# cos_POC.net
KiCad netlist of a schematic drawn in EAGLE
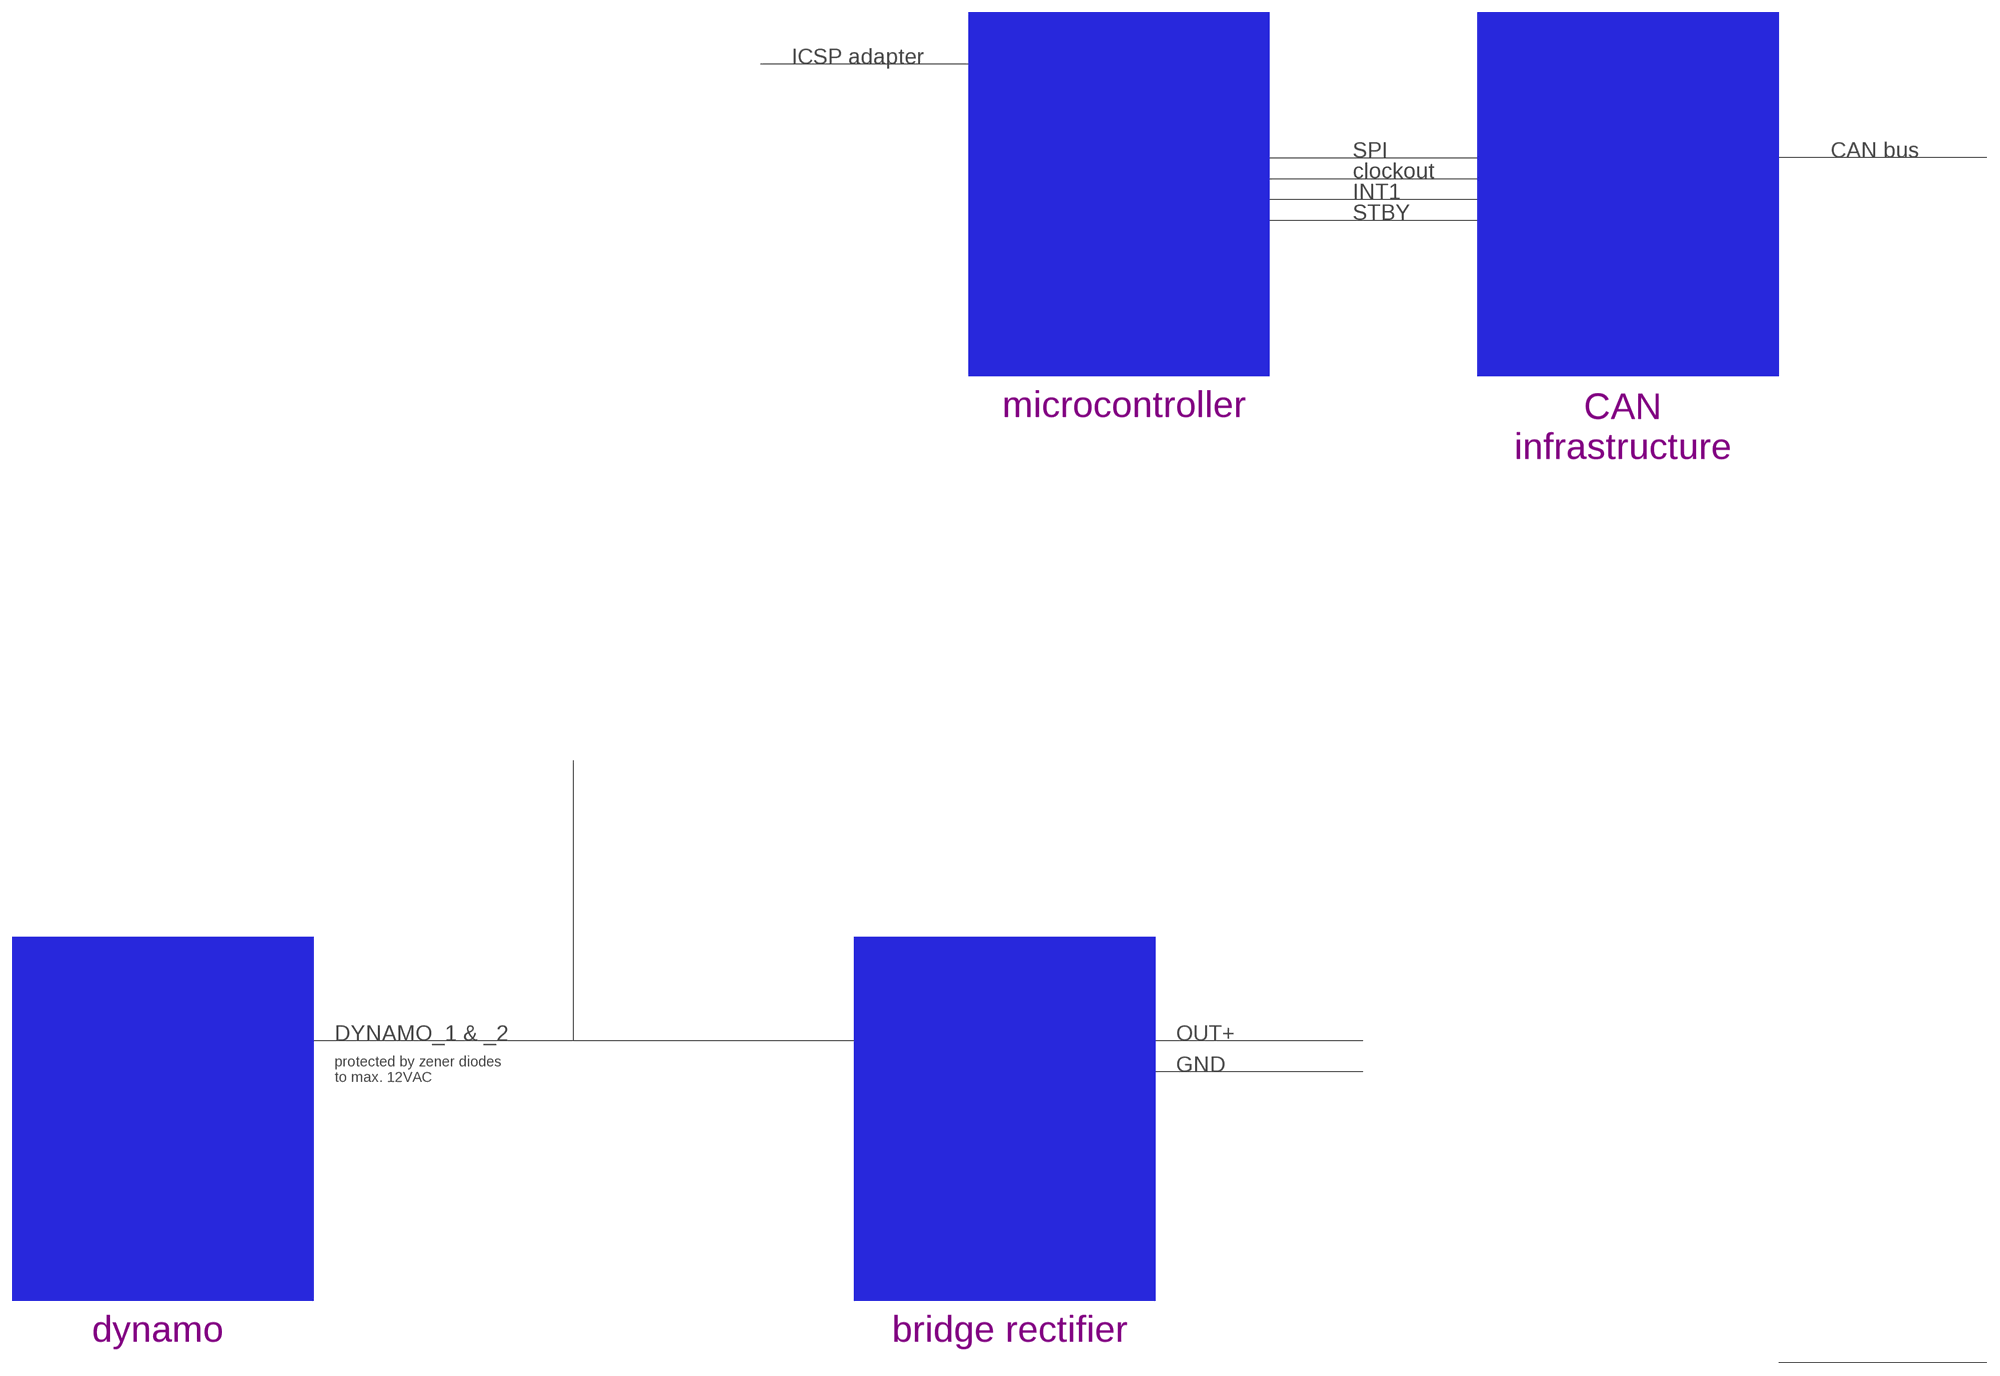
[diagram p0: schematic, sheet 1, part 1 of 3]
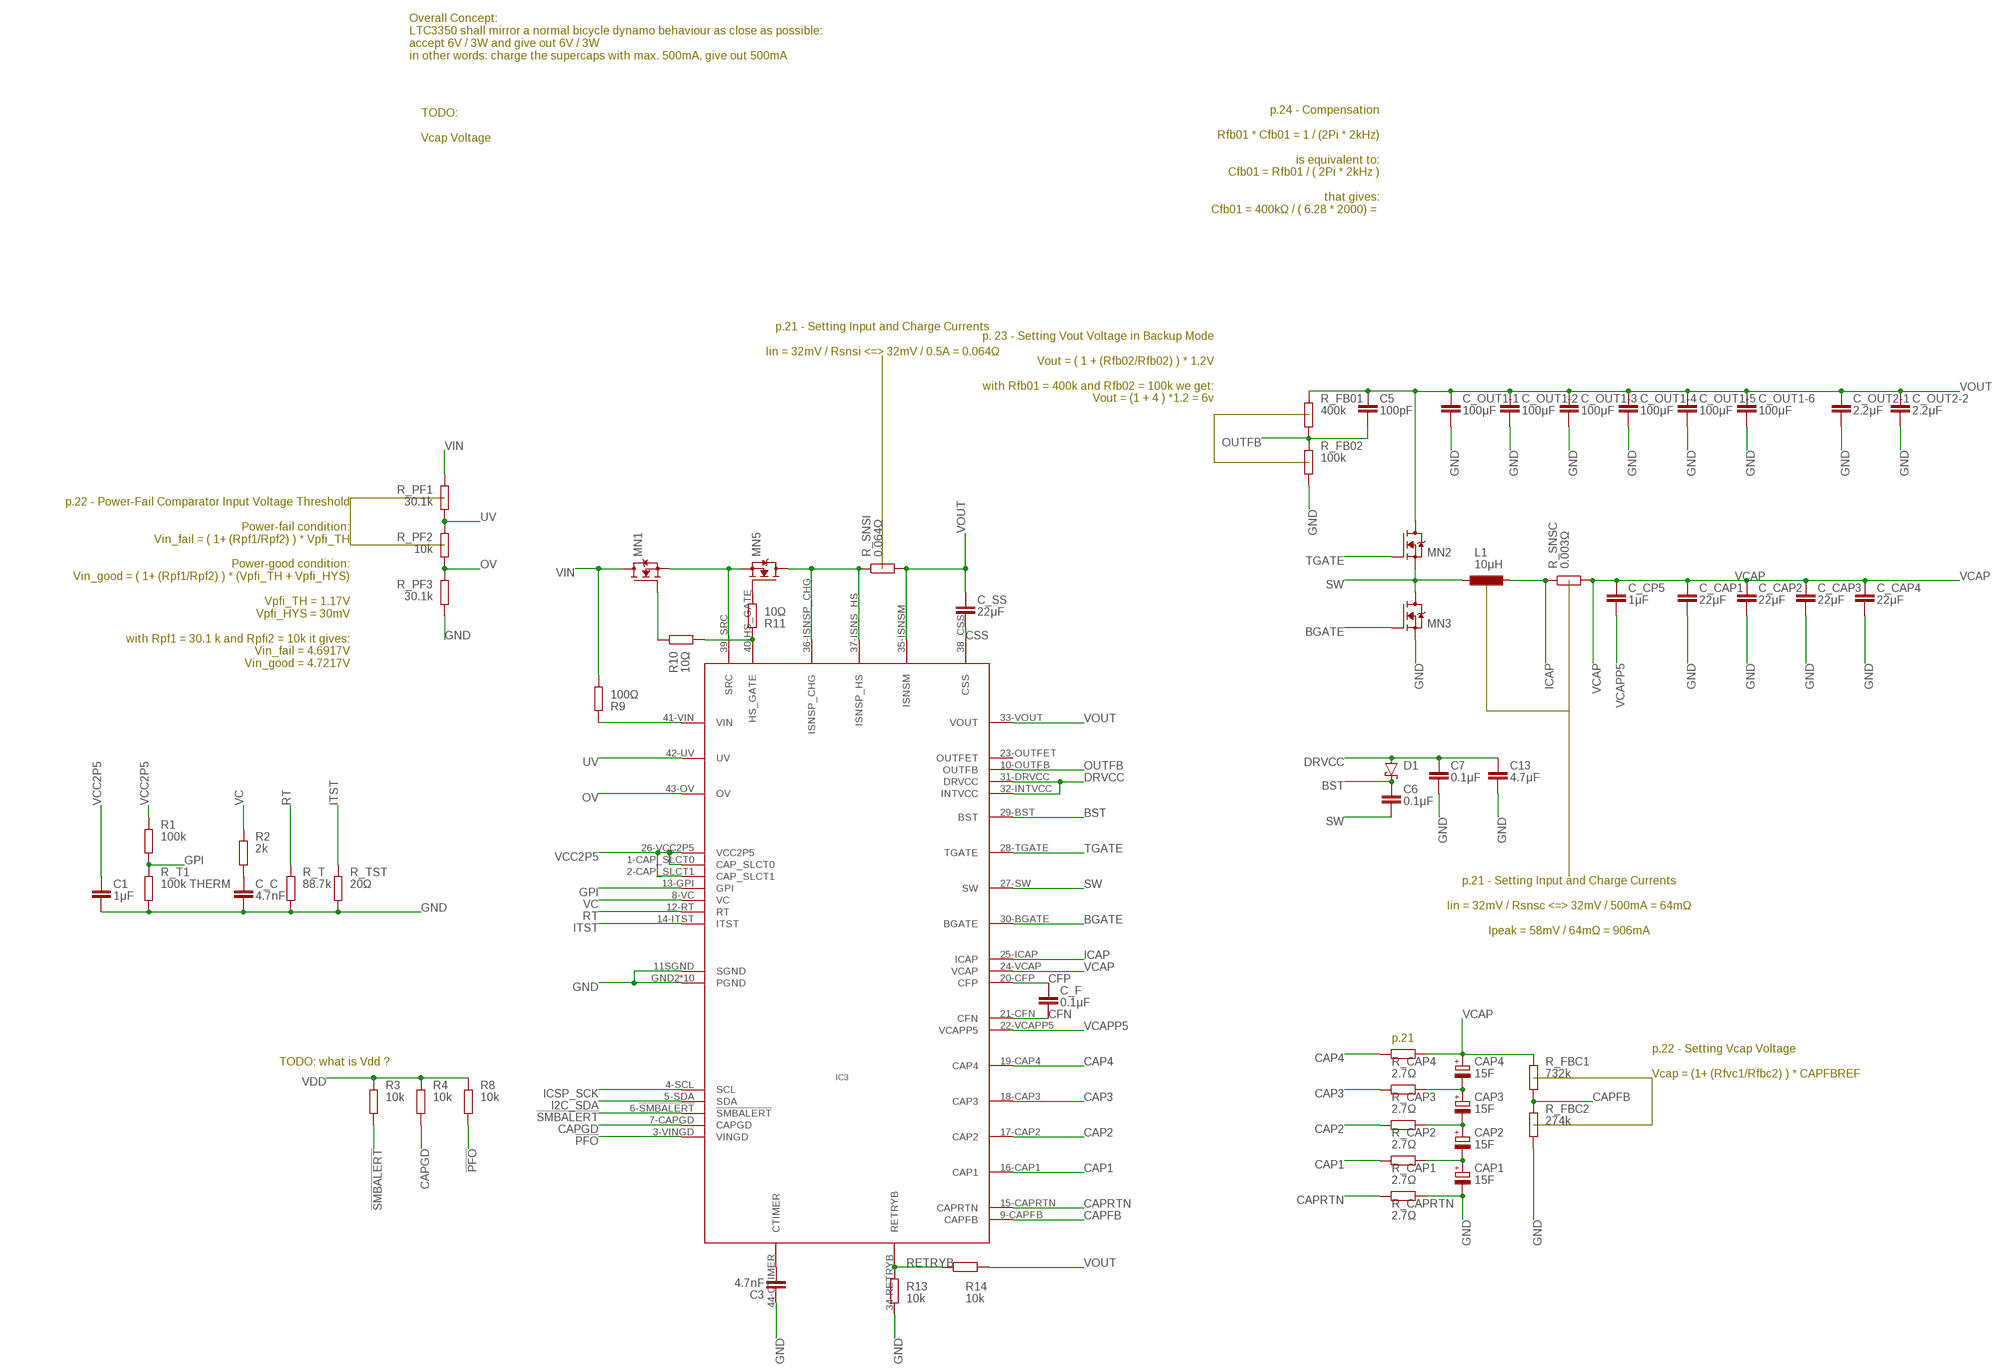
[diagram p1: schematic, sheet 1, part 2 of 3]
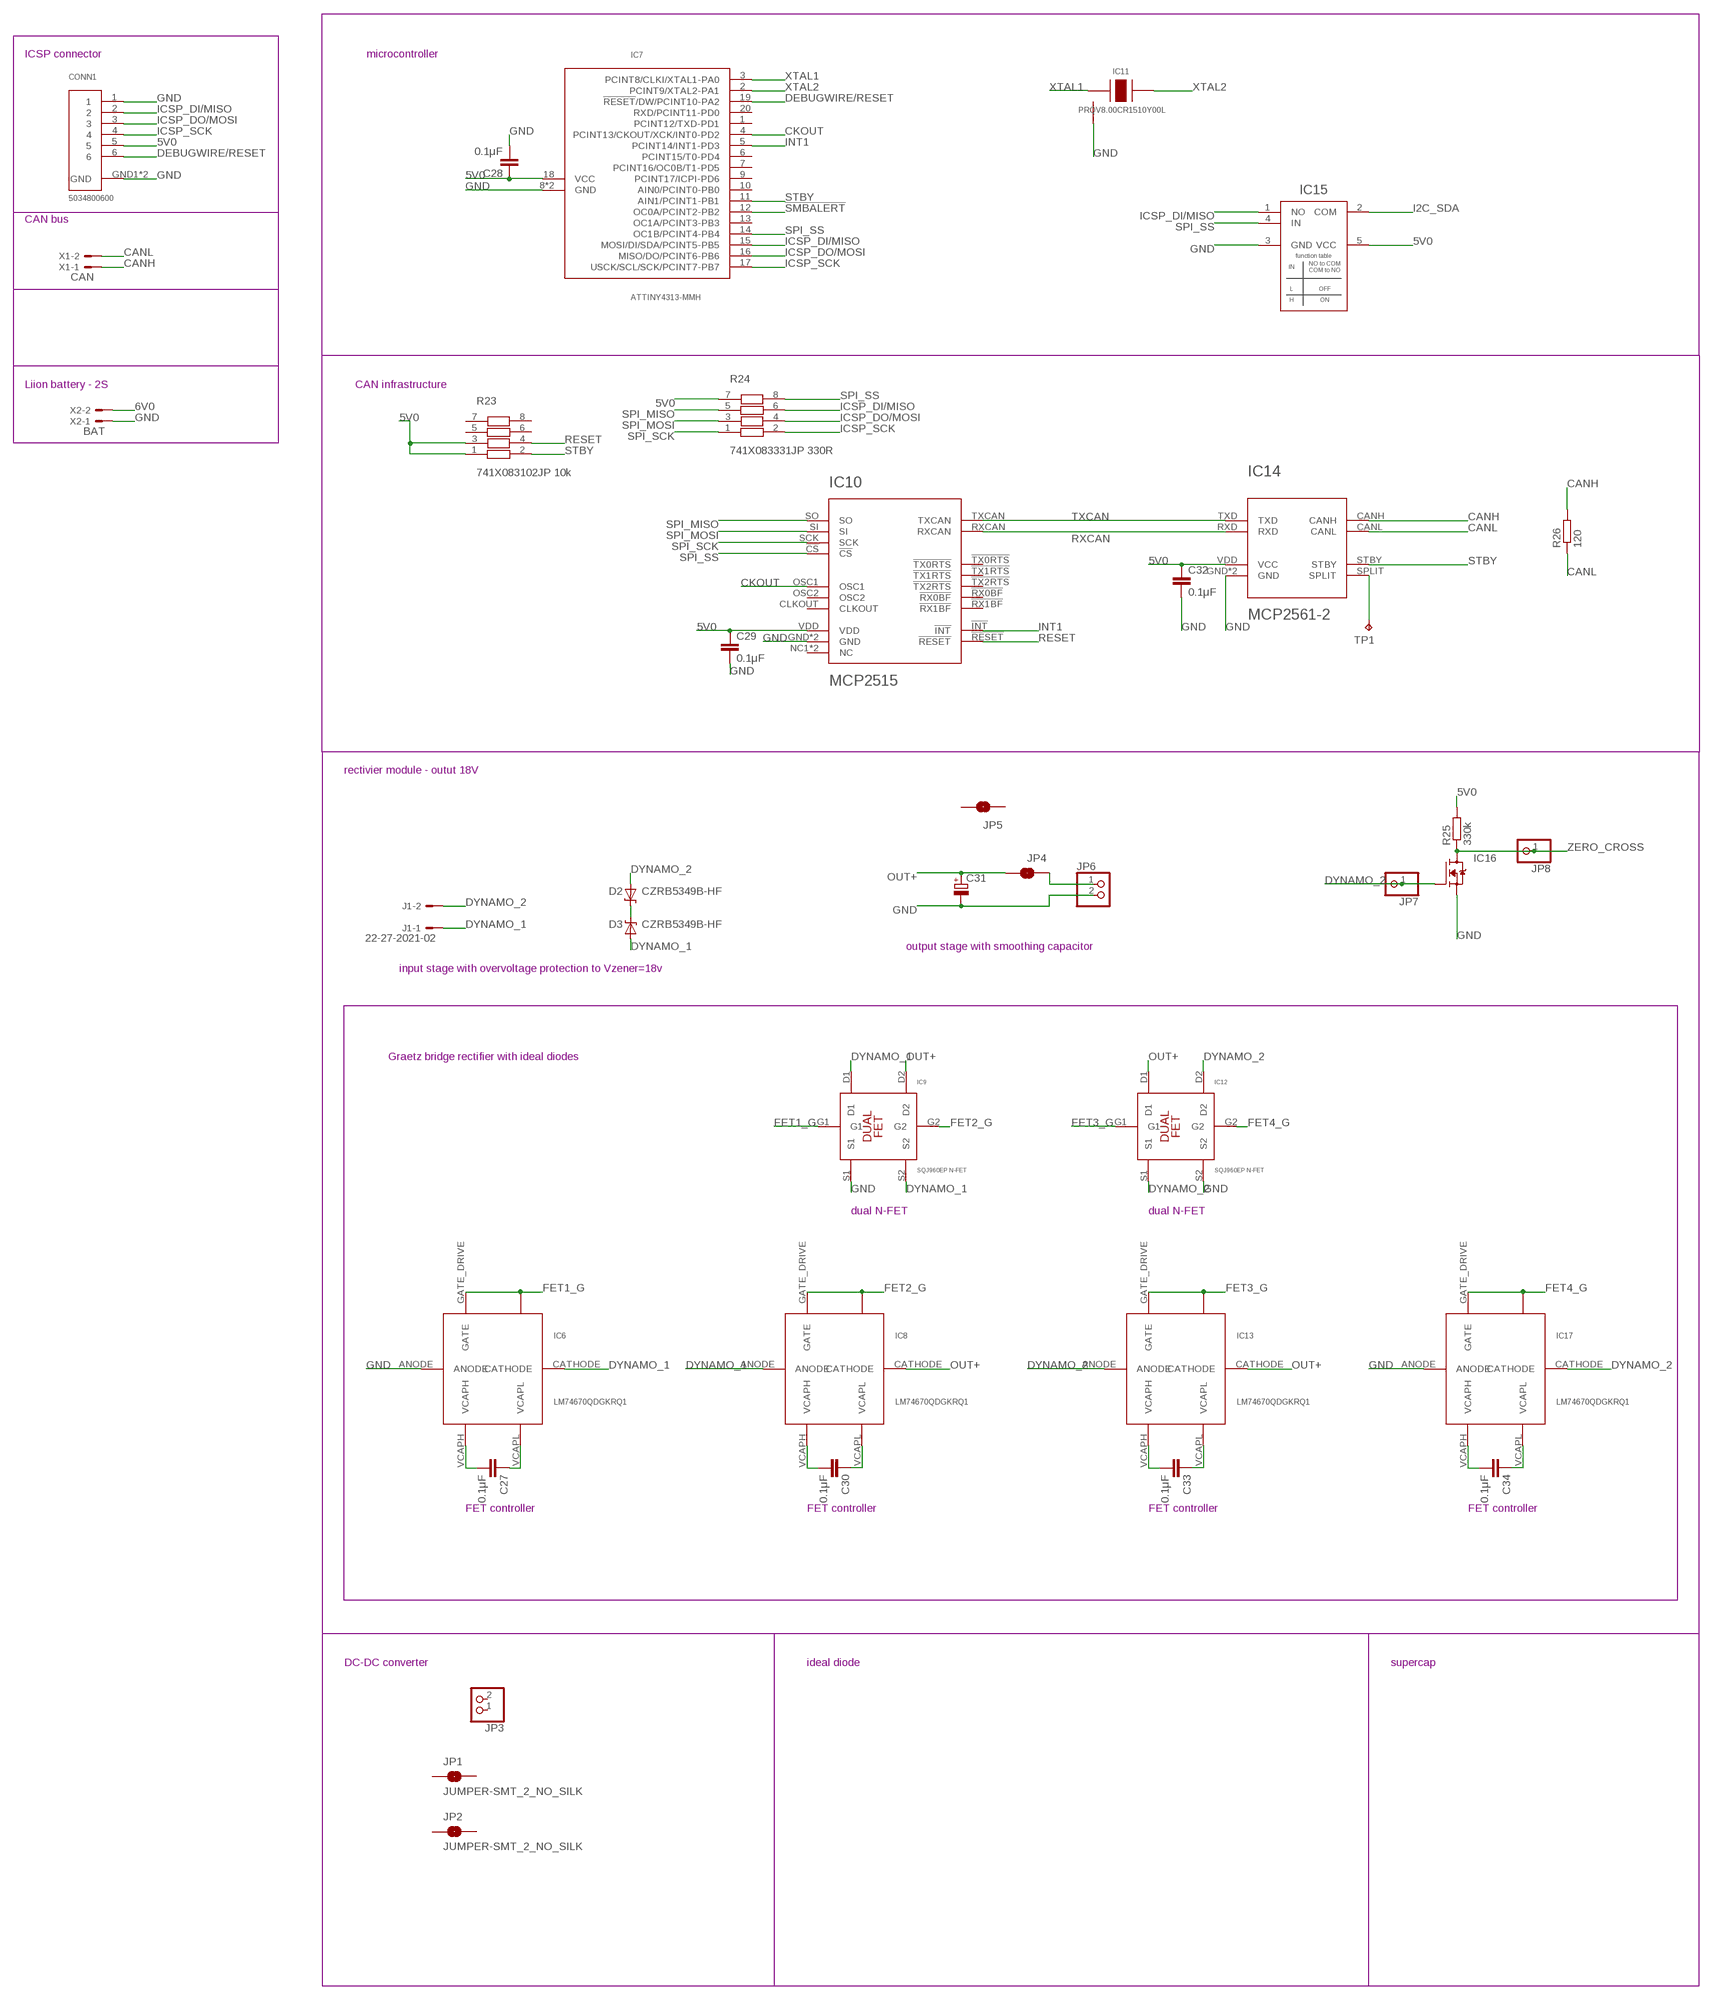
[diagram p2: schematic, sheet 1, part 3 of 3]

(export (version "E")
  (design (tool "Eeschema 10.0.6"))
  (components
    (comp (ref "C1")
      (value "1μF")
      (footprint "eagle-import:C0402")
      (libsource (lib "eagle-import") (part "C-EUC0402"))
    )
    (comp (ref "C3")
      (value "4.7nF")
      (footprint "eagle-import:C0402")
      (libsource (lib "eagle-import") (part "C-EUC0402"))
    )
    (comp (ref "C5")
      (value "100pF")
      (footprint "eagle-import:C0402")
      (libsource (lib "eagle-import") (part "C-EUC0402"))
    )
    (comp (ref "C6")
      (value "0.1μF")
      (footprint "eagle-import:C0402")
      (libsource (lib "eagle-import") (part "C-EUC0402"))
    )
    (comp (ref "C7")
      (value "0.1μF")
      (footprint "eagle-import:C0402")
      (libsource (lib "eagle-import") (part "C-EUC0402"))
    )
    (comp (ref "C13")
      (value "4.7μF")
      (footprint "eagle-import:C0402")
      (libsource (lib "eagle-import") (part "C-EUC0402"))
    )
    (comp (ref "C27")
      (value "0.1μF")
      (footprint "eagle-import:C0805")
      (libsource (lib "eagle-import") (part "C-EUC0805"))
    )
    (comp (ref "C28")
      (value "0.1μF")
      (footprint "eagle-import:C0402")
      (libsource (lib "eagle-import") (part "C-EUC0402"))
    )
    (comp (ref "C29")
      (value "0.1μF")
      (footprint "eagle-import:C0402")
      (libsource (lib "eagle-import") (part "C-EUC0402"))
    )
    (comp (ref "C30")
      (value "0.1μF")
      (footprint "eagle-import:C0805")
      (libsource (lib "eagle-import") (part "C-EUC0805"))
    )
    (comp (ref "C31")
      (value "CPOL-EUB45181A")
      (footprint "eagle-import:B45181A")
      (libsource (lib "eagle-import") (part "CPOL-EUB45181A"))
    )
    (comp (ref "C32")
      (value "0.1μF")
      (footprint "eagle-import:C0402")
      (libsource (lib "eagle-import") (part "C-EUC0402"))
    )
    (comp (ref "C33")
      (value "0.1μF")
      (footprint "eagle-import:C0805")
      (libsource (lib "eagle-import") (part "C-EUC0805"))
    )
    (comp (ref "C34")
      (value "0.1μF")
      (footprint "eagle-import:C0805")
      (libsource (lib "eagle-import") (part "C-EUC0805"))
    )
    (comp (ref "CAP1")
      (value "15F")
      (footprint "eagle-import:E5-8,5")
      (libsource (lib "eagle-import") (part "CPOL-EUE5-8.5"))
    )
    (comp (ref "CAP2")
      (value "15F")
      (footprint "eagle-import:E5-8,5")
      (libsource (lib "eagle-import") (part "CPOL-EUE5-8.5"))
    )
    (comp (ref "CAP3")
      (value "15F")
      (footprint "eagle-import:E5-8,5")
      (libsource (lib "eagle-import") (part "CPOL-EUE5-8.5"))
    )
    (comp (ref "CAP4")
      (value "15F")
      (footprint "eagle-import:E5-8,5")
      (libsource (lib "eagle-import") (part "CPOL-EUE5-8.5"))
    )
    (comp (ref "CONN1")
      (value "5034800600")
      (footprint "eagle-import:SMT")
      (libsource (lib "eagle-import") (part "5034800600"))
    )
    (comp (ref "C_C")
      (value "4.7nF")
      (footprint "eagle-import:C0402")
      (libsource (lib "eagle-import") (part "C-EUC0402"))
    )
    (comp (ref "C_CAP1")
      (value "22μF")
      (footprint "eagle-import:C0402")
      (libsource (lib "eagle-import") (part "C-EUC0402"))
    )
    (comp (ref "C_CAP2")
      (value "22μF")
      (footprint "eagle-import:C0402")
      (libsource (lib "eagle-import") (part "C-EUC0402"))
    )
    (comp (ref "C_CAP3")
      (value "22μF")
      (footprint "eagle-import:C0402")
      (libsource (lib "eagle-import") (part "C-EUC0402"))
    )
    (comp (ref "C_CAP4")
      (value "22μF")
      (footprint "eagle-import:C0402")
      (libsource (lib "eagle-import") (part "C-EUC0402"))
    )
    (comp (ref "C_CP5")
      (value "1μF")
      (footprint "eagle-import:C0402")
      (libsource (lib "eagle-import") (part "C-EUC0402"))
    )
    (comp (ref "C_F")
      (value "0.1μF")
      (footprint "eagle-import:C0402")
      (libsource (lib "eagle-import") (part "C-EUC0402"))
    )
    (comp (ref "C_OUT1-1")
      (value "100μF")
      (footprint "eagle-import:C0402")
      (libsource (lib "eagle-import") (part "C-EUC0402"))
    )
    (comp (ref "C_OUT1-2")
      (value "100μF")
      (footprint "eagle-import:C0402")
      (libsource (lib "eagle-import") (part "C-EUC0402"))
    )
    (comp (ref "C_OUT1-3")
      (value "100μF")
      (footprint "eagle-import:C0402")
      (libsource (lib "eagle-import") (part "C-EUC0402"))
    )
    (comp (ref "C_OUT1-4")
      (value "100μF")
      (footprint "eagle-import:C0402")
      (libsource (lib "eagle-import") (part "C-EUC0402"))
    )
    (comp (ref "C_OUT1-5")
      (value "100μF")
      (footprint "eagle-import:C0402")
      (libsource (lib "eagle-import") (part "C-EUC0402"))
    )
    (comp (ref "C_OUT1-6")
      (value "100μF")
      (footprint "eagle-import:C0402")
      (libsource (lib "eagle-import") (part "C-EUC0402"))
    )
    (comp (ref "C_OUT2-1")
      (value "2.2μF")
      (footprint "eagle-import:C0402")
      (libsource (lib "eagle-import") (part "C-EUC0402"))
    )
    (comp (ref "C_OUT2-2")
      (value "2.2μF")
      (footprint "eagle-import:C0402")
      (libsource (lib "eagle-import") (part "C-EUC0402"))
    )
    (comp (ref "C_SS")
      (value "22μF")
      (footprint "eagle-import:C0402")
      (libsource (lib "eagle-import") (part "C-EUC0402"))
    )
    (comp (ref "D1")
      (value "SCHOTTKY-DIODESMC")
      (footprint "eagle-import:SMC")
      (libsource (lib "eagle-import") (part "SCHOTTKY-DIODESMC"))
    )
    (comp (ref "D2")
      (value "CZRB5349B-HF")
      (footprint "eagle-import:DO-214")
      (libsource (lib "eagle-import") (part "ZENER"))
    )
    (comp (ref "D3")
      (value "CZRB5349B-HF")
      (footprint "eagle-import:DO-214")
      (libsource (lib "eagle-import") (part "ZENER"))
    )
    (comp (ref "IC3")
      (value "LTC3351")
      (footprint "eagle-import:QFN44")
      (libsource (lib "eagle-import") (part "LTC3351"))
    )
    (comp (ref "IC6")
      (value "LM74670QDGKRQ1")
      (footprint "eagle-import:VSSOP-8")
      (libsource (lib "eagle-import") (part "LM74670"))
    )
    (comp (ref "IC7")
      (value "ATTINY4313-MMH")
      (footprint "eagle-import:VQFN-20")
      (libsource (lib "eagle-import") (part "ATTINY4313VQFN-20"))
    )
    (comp (ref "IC8")
      (value "LM74670QDGKRQ1")
      (footprint "eagle-import:VSSOP-8")
      (libsource (lib "eagle-import") (part "LM74670"))
    )
    (comp (ref "IC9")
      (value "SQJ960EP N-FET")
      (footprint "eagle-import:SO-8L")
      (libsource (lib "eagle-import") (part "SQJ96XEP"))
    )
    (comp (ref "IC10")
      (value "MCP2515")
      (footprint "eagle-import:QFN20")
      (libsource (lib "eagle-import") (part "MCP2515-I-ML"))
    )
    (comp (ref "IC11")
      (value "PRQV8.00CR1510Y00L")
      (footprint "eagle-import:SMT")
      (libsource (lib "eagle-import") (part "PRQV"))
    )
    (comp (ref "IC12")
      (value "SQJ960EP N-FET")
      (footprint "eagle-import:SO-8L")
      (libsource (lib "eagle-import") (part "SQJ96XEP"))
    )
    (comp (ref "IC13")
      (value "LM74670QDGKRQ1")
      (footprint "eagle-import:VSSOP-8")
      (libsource (lib "eagle-import") (part "LM74670"))
    )
    (comp (ref "IC14")
      (value "MCP2561-2")
      (footprint "eagle-import:DFN10")
      (libsource (lib "eagle-import") (part "MCP2561-2"))
    )
    (comp (ref "IC15")
      (value "TS5A1066SOT-23")
      (footprint "eagle-import:SOT-23")
      (libsource (lib "eagle-import") (part "TS5A1066SOT-23"))
    )
    (comp (ref "IC16")
      (value "SIA456DJ")
      (footprint "eagle-import:SC-70-6")
      (libsource (lib "eagle-import") (part "SIA456DJ"))
    )
    (comp (ref "IC17")
      (value "LM74670QDGKRQ1")
      (footprint "eagle-import:VSSOP-8")
      (libsource (lib "eagle-import") (part "LM74670"))
    )
    (comp (ref "J1")
      (value "22-27-2021-02")
      (footprint "eagle-import:6410-02")
      (fields (field (name "MF") "MOLEX"))
      (libsource (lib "eagle-import") (part "22-?-0227-2021"))
    )
    (comp (ref "JP1")
      (value "JUMPER-SMT_2_NO_SILK")
      (footprint "eagle-import:SMT-JUMPER_2_NO_SILK")
      (libsource (lib "eagle-import") (part "JUMPER-SMT_2_NO_SILK"))
    )
    (comp (ref "JP2")
      (value "JUMPER-SMT_2_NO_SILK")
      (footprint "eagle-import:SMT-JUMPER_2_NO_SILK")
      (libsource (lib "eagle-import") (part "JUMPER-SMT_2_NO_SILK"))
    )
    (comp (ref "JP3")
      (value "PINHD-1X2")
      (footprint "eagle-import:1X02")
      (libsource (lib "eagle-import") (part "PINHD-1X2"))
    )
    (comp (ref "JP4")
      (value "JUMPER-SMT_2_NO_SILK")
      (footprint "eagle-import:SMT-JUMPER_2_NO_SILK")
      (libsource (lib "eagle-import") (part "JUMPER-SMT_2_NO_SILK"))
    )
    (comp (ref "JP5")
      (value "JUMPER-SMT_2_NO_SILK")
      (footprint "eagle-import:SMT-JUMPER_2_NO_SILK")
      (libsource (lib "eagle-import") (part "JUMPER-SMT_2_NO_SILK"))
    )
    (comp (ref "JP6")
      (value "PINHD-1X2")
      (footprint "eagle-import:1X02")
      (libsource (lib "eagle-import") (part "PINHD-1X2"))
    )
    (comp (ref "JP7")
      (value "PINHD-1X1")
      (footprint "eagle-import:1X01")
      (libsource (lib "eagle-import") (part "PINHD-1X1"))
    )
    (comp (ref "JP8")
      (value "PINHD-1X1")
      (footprint "eagle-import:1X01")
      (libsource (lib "eagle-import") (part "PINHD-1X1"))
    )
    (comp (ref "L1")
      (value "10μH")
      (footprint "eagle-import:L1812")
      (libsource (lib "eagle-import") (part "L-EUL1812"))
    )
    (comp (ref "MN1")
      (value "SIA456DJ")
      (footprint "eagle-import:SC-70-6")
      (libsource (lib "eagle-import") (part "SIA456DJ"))
    )
    (comp (ref "MN2")
      (value "SIA456DJ")
      (footprint "eagle-import:SC-70-6")
      (libsource (lib "eagle-import") (part "SIA456DJ"))
    )
    (comp (ref "MN3")
      (value "SIA456DJ")
      (footprint "eagle-import:SC-70-6")
      (libsource (lib "eagle-import") (part "SIA456DJ"))
    )
    (comp (ref "MN5")
      (value "SIA456DJ")
      (footprint "eagle-import:SC-70-6")
      (libsource (lib "eagle-import") (part "SIA456DJ"))
    )
    (comp (ref "R1")
      (value "100k")
      (footprint "eagle-import:R0402")
      (libsource (lib "eagle-import") (part "R-EU_R0402"))
    )
    (comp (ref "R2")
      (value "2k")
      (footprint "eagle-import:R0402")
      (libsource (lib "eagle-import") (part "R-EU_R0402"))
    )
    (comp (ref "R3")
      (value "10k")
      (footprint "eagle-import:R0402")
      (libsource (lib "eagle-import") (part "R-EU_R0402"))
    )
    (comp (ref "R4")
      (value "10k")
      (footprint "eagle-import:R0402")
      (libsource (lib "eagle-import") (part "R-EU_R0402"))
    )
    (comp (ref "R8")
      (value "10k")
      (footprint "eagle-import:R0402")
      (libsource (lib "eagle-import") (part "R-EU_R0402"))
    )
    (comp (ref "R9")
      (value "100Ω")
      (footprint "eagle-import:R0402")
      (libsource (lib "eagle-import") (part "R-EU_R0402"))
    )
    (comp (ref "R10")
      (value "10Ω")
      (footprint "eagle-import:R0402")
      (libsource (lib "eagle-import") (part "R-EU_R0402"))
    )
    (comp (ref "R11")
      (value "10Ω")
      (footprint "eagle-import:R0402")
      (libsource (lib "eagle-import") (part "R-EU_R0402"))
    )
    (comp (ref "R13")
      (value "10k")
      (footprint "eagle-import:R0402")
      (libsource (lib "eagle-import") (part "R-EU_R0402"))
    )
    (comp (ref "R14")
      (value "10k")
      (footprint "eagle-import:R0402")
      (libsource (lib "eagle-import") (part "R-EU_R0402"))
    )
    (comp (ref "R23")
      (value "741X083102JP 10k")
      (footprint "eagle-import:0402-4R")
      (libsource (lib "eagle-import") (part "741X083331JP"))
    )
    (comp (ref "R24")
      (value "741X083331JP 330R")
      (footprint "eagle-import:0402-4R")
      (libsource (lib "eagle-import") (part "741X083331JP"))
    )
    (comp (ref "R25")
      (value "330k")
      (footprint "eagle-import:R0805")
      (libsource (lib "eagle-import") (part "R-EU_R0805"))
    )
    (comp (ref "R26")
      (value "120")
      (footprint "eagle-import:R0805")
      (libsource (lib "eagle-import") (part "R-EU_R0805"))
    )
    (comp (ref "R_CAP1")
      (value "2.7Ω")
      (footprint "eagle-import:R0402")
      (libsource (lib "eagle-import") (part "R-EU_R0402"))
    )
    (comp (ref "R_CAP2")
      (value "2.7Ω")
      (footprint "eagle-import:R0402")
      (libsource (lib "eagle-import") (part "R-EU_R0402"))
    )
    (comp (ref "R_CAP3")
      (value "2.7Ω")
      (footprint "eagle-import:R0402")
      (libsource (lib "eagle-import") (part "R-EU_R0402"))
    )
    (comp (ref "R_CAP4")
      (value "2.7Ω")
      (footprint "eagle-import:R0402")
      (libsource (lib "eagle-import") (part "R-EU_R0402"))
    )
    (comp (ref "R_CAPRTN")
      (value "2.7Ω")
      (footprint "eagle-import:R0402")
      (libsource (lib "eagle-import") (part "R-EU_R0402"))
    )
    (comp (ref "R_FB01")
      (value "400k")
      (footprint "eagle-import:R0402")
      (libsource (lib "eagle-import") (part "R-EU_R0402"))
    )
    (comp (ref "R_FB02")
      (value "100k")
      (footprint "eagle-import:R0402")
      (libsource (lib "eagle-import") (part "R-EU_R0402"))
    )
    (comp (ref "R_FBC1")
      (value "732k")
      (footprint "eagle-import:R0402")
      (libsource (lib "eagle-import") (part "R-EU_R0402"))
    )
    (comp (ref "R_FBC2")
      (value "274k")
      (footprint "eagle-import:R0402")
      (libsource (lib "eagle-import") (part "R-EU_R0402"))
    )
    (comp (ref "R_PF1")
      (value "30.1k")
      (footprint "eagle-import:R0402")
      (libsource (lib "eagle-import") (part "R-EU_R0402"))
    )
    (comp (ref "R_PF2")
      (value "10k")
      (footprint "eagle-import:R0402")
      (libsource (lib "eagle-import") (part "R-EU_R0402"))
    )
    (comp (ref "R_PF3")
      (value "30.1k")
      (footprint "eagle-import:R0402")
      (libsource (lib "eagle-import") (part "R-EU_R0402"))
    )
    (comp (ref "R_SNSC")
      (value "0.003Ω")
      (footprint "eagle-import:R0402")
      (libsource (lib "eagle-import") (part "R-EU_R0402"))
    )
    (comp (ref "R_SNSI")
      (value "0.064Ω")
      (footprint "eagle-import:R0402")
      (libsource (lib "eagle-import") (part "R-EU_R0402"))
    )
    (comp (ref "R_T")
      (value "88.7k")
      (footprint "eagle-import:R0402")
      (libsource (lib "eagle-import") (part "R-EU_R0402"))
    )
    (comp (ref "R_T1")
      (value "100k THERM")
      (footprint "eagle-import:R0402")
      (libsource (lib "eagle-import") (part "R-EU_R0402"))
    )
    (comp (ref "R_TST")
      (value "20Ω")
      (footprint "eagle-import:R0402")
      (libsource (lib "eagle-import") (part "R-EU_R0402"))
    )
    (comp (ref "TP1")
      (value "TPB2,54")
      (footprint "eagle-import:B2,54")
      (libsource (lib "eagle-import") (part "TPB2,54"))
    )
    (comp (ref "X1")
      (value "CAN")
      (footprint "eagle-import:22-23-2021")
      (fields (field (name "MF") "MOLEX") (field (name "MPN") "22-23-2021"))
      (libsource (lib "eagle-import") (part "22-23-2021"))
    )
    (comp (ref "X2")
      (value "BAT")
      (footprint "eagle-import:22-23-2021")
      (fields (field (name "MF") "MOLEX") (field (name "MPN") "22-23-2021"))
      (libsource (lib "eagle-import") (part "22-23-2021"))
    )
  )
  (nets
    (net (code "1") (name "/5V0") (class "Default")
      (node (ref "C28") (pin "1") (pinfunction "1_1") (pintype "passive"))
      (node (ref "C29") (pin "1") (pinfunction "1_1") (pintype "passive"))
      (node (ref "C32") (pin "1") (pinfunction "1_1") (pintype "passive"))
      (node (ref "CONN1") (pin "5") (pinfunction "5_5") (pintype "bidirectional"))
      (node (ref "IC10") (pin "VDD") (pinfunction "VDD_VDD") (pintype "power_in"))
      (node (ref "IC14") (pin "VDD") (pinfunction "VCC_VDD") (pintype "power_in"))
      (node (ref "IC15") (pin "5") (pinfunction "VCC_5") (pintype "bidirectional"))
      (node (ref "IC7") (pin "18") (pinfunction "VCC_18") (pintype "bidirectional"))
      (node (ref "R23") (pin "1") (pinfunction "1_1") (pintype "bidirectional"))
      (node (ref "R23") (pin "3") (pinfunction "3_3") (pintype "bidirectional"))
      (node (ref "R24") (pin "7") (pinfunction "7_7") (pintype "bidirectional"))
      (node (ref "R25") (pin "2") (pinfunction "2_2") (pintype "passive"))
    )
    (net (code "2") (name "/6V0") (class "Default")
      (node (ref "X2") (pin "2") (pinfunction "S_2") (pintype "passive"))
    )
    (net (code "3") (name "/BGATE") (class "Default")
      (node (ref "IC3") (pin "30-BGATE") (pinfunction "BGATE_30-BGATE") (pintype "bidirectional"))
      (node (ref "MN3") (pin "3G") (pinfunction "G_3G") (pintype "passive"))
    )
    (net (code "4") (name "/BST") (class "Default")
      (node (ref "C6") (pin "1") (pinfunction "1_1") (pintype "passive"))
      (node (ref "D1") (pin "C") (pinfunction "C_C") (pintype "passive"))
      (node (ref "IC3") (pin "29-BST") (pinfunction "BST_29-BST") (pintype "bidirectional"))
    )
    (net (code "5") (name "/CANH") (class "Default")
      (node (ref "IC14") (pin "CANH") (pinfunction "CANH_CANH") (pintype "bidirectional"))
      (node (ref "R26") (pin "2") (pinfunction "2_2") (pintype "passive"))
      (node (ref "X1") (pin "1") (pinfunction "S_1") (pintype "passive"))
    )
    (net (code "6") (name "/CANL") (class "Default")
      (node (ref "IC14") (pin "CANL") (pinfunction "CANL_CANL") (pintype "bidirectional"))
      (node (ref "R26") (pin "1") (pinfunction "1_1") (pintype "passive"))
      (node (ref "X1") (pin "2") (pinfunction "S_2") (pintype "passive"))
    )
    (net (code "7") (name "/CAP1") (class "Default")
      (node (ref "IC3") (pin "16-CAP1") (pinfunction "CAP1_16-CAP1") (pintype "bidirectional"))
      (node (ref "R_CAP1") (pin "1") (pinfunction "1_1") (pintype "passive"))
    )
    (net (code "8") (name "/CAP2") (class "Default")
      (node (ref "IC3") (pin "17-CAP2") (pinfunction "CAP2_17-CAP2") (pintype "bidirectional"))
      (node (ref "R_CAP2") (pin "1") (pinfunction "1_1") (pintype "passive"))
    )
    (net (code "9") (name "/CAP3") (class "Default")
      (node (ref "IC3") (pin "18-CAP3") (pinfunction "CAP3_18-CAP3") (pintype "bidirectional"))
      (node (ref "R_CAP3") (pin "1") (pinfunction "1_1") (pintype "passive"))
    )
    (net (code "10") (name "/CAP4") (class "Default")
      (node (ref "IC3") (pin "19-CAP4") (pinfunction "CAP4_19-CAP4") (pintype "bidirectional"))
      (node (ref "R_CAP4") (pin "1") (pinfunction "1_1") (pintype "passive"))
    )
    (net (code "11") (name "/CAPFB") (class "Default")
      (node (ref "IC3") (pin "9-CAPFB") (pinfunction "CAPFB_9-CAPFB") (pintype "bidirectional"))
      (node (ref "R_FBC1") (pin "1") (pinfunction "1_1") (pintype "passive"))
      (node (ref "R_FBC2") (pin "2") (pinfunction "2_2") (pintype "passive"))
    )
    (net (code "12") (name "/CAPGD") (class "Default")
      (node (ref "IC3") (pin "7-CAPGD") (pinfunction "CAPGD_7-CAPGD") (pintype "output"))
      (node (ref "R4") (pin "2") (pinfunction "2_2") (pintype "passive"))
    )
    (net (code "13") (name "/CAPRTN") (class "Default")
      (node (ref "IC3") (pin "15-CAPRTN") (pinfunction "CAPRTN_15-CAPRTN") (pintype "bidirectional"))
      (node (ref "R_CAPRTN") (pin "1") (pinfunction "1_1") (pintype "passive"))
    )
    (net (code "14") (name "/CFN") (class "Default")
      (node (ref "C_F") (pin "2") (pinfunction "2_2") (pintype "passive"))
      (node (ref "IC3") (pin "21-CFN") (pinfunction "CFN_21-CFN") (pintype "bidirectional"))
    )
    (net (code "15") (name "/CFP") (class "Default")
      (node (ref "C_F") (pin "1") (pinfunction "1_1") (pintype "passive"))
      (node (ref "IC3") (pin "20-CFP") (pinfunction "CFP_20-CFP") (pintype "bidirectional"))
    )
    (net (code "16") (name "/CKOUT") (class "Default")
      (node (ref "IC10") (pin "OSC1") (pinfunction "OSC1_OSC1") (pintype "bidirectional"))
      (node (ref "IC7") (pin "4") (pinfunction "PCINT13/CKOUT/XCK/INT0-PD2_4") (pintype "bidirectional"))
    )
    (net (code "17") (name "/CSS") (class "Default")
      (node (ref "C_SS") (pin "2") (pinfunction "2_2") (pintype "passive"))
      (node (ref "IC3") (pin "38_CSS") (pinfunction "CSS_38_CSS") (pintype "bidirectional"))
    )
    (net (code "18") (name "/DEBUGWIRE{slash}RESET") (class "Default")
      (node (ref "CONN1") (pin "6") (pinfunction "6_6") (pintype "bidirectional"))
      (node (ref "IC7") (pin "19") (pinfunction "~{RESET}/DW/PCINT10-PA2_19") (pintype "bidirectional"))
    )
    (net (code "19") (name "/DRVCC") (class "Default")
      (node (ref "C13") (pin "1") (pinfunction "1_1") (pintype "passive"))
      (node (ref "C7") (pin "1") (pinfunction "1_1") (pintype "passive"))
      (node (ref "D1") (pin "A") (pinfunction "A_A") (pintype "passive"))
      (node (ref "IC3") (pin "31-DRVCC") (pinfunction "DRVCC_31-DRVCC") (pintype "bidirectional"))
      (node (ref "IC3") (pin "32-INTVCC") (pinfunction "INTVCC_32-INTVCC") (pintype "bidirectional"))
    )
    (net (code "20") (name "/DYNAMO_1") (class "Default")
      (node (ref "D3") (pin "AN") (pinfunction "AN_AN") (pintype "passive"))
      (node (ref "IC6") (pin "CATHODE") (pinfunction "CATHODE_CATHODE") (pintype "bidirectional"))
      (node (ref "IC8") (pin "ANODE") (pinfunction "ANODE_ANODE") (pintype "bidirectional"))
      (node (ref "IC9") (pin "D1") (pinfunction "D1_D1") (pintype "bidirectional"))
      (node (ref "IC9") (pin "S2") (pinfunction "S2_S2") (pintype "bidirectional"))
      (node (ref "J1") (pin "1") (pinfunction "S_1") (pintype "passive"))
    )
    (net (code "21") (name "/DYNAMO_2") (class "Default")
      (node (ref "D2") (pin "AN") (pinfunction "AN_AN") (pintype "passive"))
      (node (ref "IC12") (pin "D2") (pinfunction "D2_D2") (pintype "bidirectional"))
      (node (ref "IC12") (pin "S1") (pinfunction "S1_S1") (pintype "bidirectional"))
      (node (ref "IC13") (pin "ANODE") (pinfunction "ANODE_ANODE") (pintype "bidirectional"))
      (node (ref "IC16") (pin "3G") (pinfunction "G_3G") (pintype "passive"))
      (node (ref "IC17") (pin "CATHODE") (pinfunction "CATHODE_CATHODE") (pintype "bidirectional"))
      (node (ref "J1") (pin "2") (pinfunction "S_2") (pintype "passive"))
      (node (ref "JP7") (pin "1") (pinfunction "1_1") (pintype "passive"))
    )
    (net (code "22") (name "/FET1_G") (class "Default")
      (node (ref "IC6") (pin "GATE_DRIVE") (pinfunction "GATE_GATE_DRIVE") (pintype "bidirectional"))
      (node (ref "IC6") (pin "GATE_PULLD") (pinfunction "GATE_PULLD_GATE_PULLD") (pintype "bidirectional"))
      (node (ref "IC9") (pin "G1") (pinfunction "G1_G1") (pintype "bidirectional"))
    )
    (net (code "23") (name "/FET2_G") (class "Default")
      (node (ref "IC8") (pin "GATE_DRIVE") (pinfunction "GATE_GATE_DRIVE") (pintype "bidirectional"))
      (node (ref "IC8") (pin "GATE_PULLD") (pinfunction "GATE_PULLD_GATE_PULLD") (pintype "bidirectional"))
      (node (ref "IC9") (pin "G2") (pinfunction "G2_G2") (pintype "bidirectional"))
    )
    (net (code "24") (name "/FET3_G") (class "Default")
      (node (ref "IC12") (pin "G1") (pinfunction "G1_G1") (pintype "bidirectional"))
      (node (ref "IC13") (pin "GATE_DRIVE") (pinfunction "GATE_GATE_DRIVE") (pintype "bidirectional"))
      (node (ref "IC13") (pin "GATE_PULLD") (pinfunction "GATE_PULLD_GATE_PULLD") (pintype "bidirectional"))
    )
    (net (code "25") (name "/FET4_G") (class "Default")
      (node (ref "IC12") (pin "G2") (pinfunction "G2_G2") (pintype "bidirectional"))
      (node (ref "IC17") (pin "GATE_DRIVE") (pinfunction "GATE_GATE_DRIVE") (pintype "bidirectional"))
      (node (ref "IC17") (pin "GATE_PULLD") (pinfunction "GATE_PULLD_GATE_PULLD") (pintype "bidirectional"))
    )
    (net (code "26") (name "/GND") (class "Default")
      (node (ref "C1") (pin "2") (pinfunction "2_2") (pintype "passive"))
      (node (ref "C13") (pin "2") (pinfunction "2_2") (pintype "passive"))
      (node (ref "C28") (pin "2") (pinfunction "2_2") (pintype "passive"))
      (node (ref "C29") (pin "2") (pinfunction "2_2") (pintype "passive"))
      (node (ref "C3") (pin "1") (pinfunction "1_1") (pintype "passive"))
      (node (ref "C31") (pin "-") (pinfunction "-_-") (pintype "passive"))
      (node (ref "C32") (pin "2") (pinfunction "2_2") (pintype "passive"))
      (node (ref "C7") (pin "2") (pinfunction "2_2") (pintype "passive"))
      (node (ref "CAP1") (pin "-") (pinfunction "-_-") (pintype "passive"))
      (node (ref "CONN1") (pin "1") (pinfunction "1_1") (pintype "bidirectional"))
      (node (ref "CONN1") (pin "GND1") (pinfunction "GND_GND1") (pintype "bidirectional"))
      (node (ref "CONN1") (pin "GND2") (pinfunction "GND_GND2") (pintype "bidirectional"))
      (node (ref "C_C") (pin "2") (pinfunction "2_2") (pintype "passive"))
      (node (ref "C_CAP1") (pin "2") (pinfunction "2_2") (pintype "passive"))
      (node (ref "C_CAP2") (pin "2") (pinfunction "2_2") (pintype "passive"))
      (node (ref "C_CAP3") (pin "2") (pinfunction "2_2") (pintype "passive"))
      (node (ref "C_CAP4") (pin "2") (pinfunction "2_2") (pintype "passive"))
      (node (ref "C_OUT1-1") (pin "2") (pinfunction "2_2") (pintype "passive"))
      (node (ref "C_OUT1-2") (pin "2") (pinfunction "2_2") (pintype "passive"))
      (node (ref "C_OUT1-3") (pin "2") (pinfunction "2_2") (pintype "passive"))
      (node (ref "C_OUT1-4") (pin "2") (pinfunction "2_2") (pintype "passive"))
      (node (ref "C_OUT1-5") (pin "2") (pinfunction "2_2") (pintype "passive"))
      (node (ref "C_OUT1-6") (pin "2") (pinfunction "2_2") (pintype "passive"))
      (node (ref "C_OUT2-1") (pin "2") (pinfunction "2_2") (pintype "passive"))
      (node (ref "C_OUT2-2") (pin "2") (pinfunction "2_2") (pintype "passive"))
      (node (ref "IC10") (pin "GND") (pinfunction "GND_GND") (pintype "power_in"))
      (node (ref "IC10") (pin "GND6") (pinfunction "GND_GND6") (pintype "power_in"))
      (node (ref "IC11") (pin "GND") (pinfunction "GND_GND") (pintype "bidirectional"))
      (node (ref "IC12") (pin "S2") (pinfunction "S2_S2") (pintype "bidirectional"))
      (node (ref "IC14") (pin "GND") (pinfunction "GND_GND") (pintype "power_in"))
      (node (ref "IC14") (pin "VSS") (pinfunction "GND_VSS") (pintype "power_in"))
      (node (ref "IC15") (pin "3") (pinfunction "GND_3") (pintype "bidirectional"))
      (node (ref "IC16") (pin "4S") (pinfunction "S_4S") (pintype "passive"))
      (node (ref "IC16") (pin "S") (pinfunction "S_S") (pintype "passive"))
      (node (ref "IC17") (pin "ANODE") (pinfunction "ANODE_ANODE") (pintype "bidirectional"))
      (node (ref "IC3") (pin "11SGND") (pinfunction "SGND_11SGND") (pintype "bidirectional"))
      (node (ref "IC3") (pin "GND10") (pinfunction "PGND_GND10") (pintype "bidirectional"))
      (node (ref "IC3") (pin "GND2") (pinfunction "PGND_GND2") (pintype "bidirectional"))
      (node (ref "IC3") (pin "GND3") (pinfunction "PGND_GND3") (pintype "bidirectional"))
      (node (ref "IC3") (pin "GND4") (pinfunction "PGND_GND4") (pintype "bidirectional"))
      (node (ref "IC3") (pin "GND5") (pinfunction "PGND_GND5") (pintype "bidirectional"))
      (node (ref "IC3") (pin "GND6") (pinfunction "PGND_GND6") (pintype "bidirectional"))
      (node (ref "IC3") (pin "GND7") (pinfunction "PGND_GND7") (pintype "bidirectional"))
      (node (ref "IC3") (pin "GND8") (pinfunction "PGND_GND8") (pintype "bidirectional"))
      (node (ref "IC3") (pin "GND9") (pinfunction "PGND_GND9") (pintype "bidirectional"))
      (node (ref "IC3") (pin "PGND") (pinfunction "PGND_PGND") (pintype "bidirectional"))
      (node (ref "IC6") (pin "ANODE") (pinfunction "ANODE_ANODE") (pintype "bidirectional"))
      (node (ref "IC7") (pin "8") (pinfunction "GND_8") (pintype "bidirectional"))
      (node (ref "IC7") (pin "GND") (pinfunction "GND_GND") (pintype "bidirectional"))
      (node (ref "IC9") (pin "S1") (pinfunction "S1_S1") (pintype "bidirectional"))
      (node (ref "JP6") (pin "2") (pinfunction "2_2") (pintype "passive"))
      (node (ref "MN3") (pin "4S") (pinfunction "S_4S") (pintype "passive"))
      (node (ref "MN3") (pin "S") (pinfunction "S_S") (pintype "passive"))
      (node (ref "R13") (pin "2") (pinfunction "2_2") (pintype "passive"))
      (node (ref "R_CAPRTN") (pin "2") (pinfunction "2_2") (pintype "passive"))
      (node (ref "R_FB02") (pin "2") (pinfunction "2_2") (pintype "passive"))
      (node (ref "R_FBC2") (pin "1") (pinfunction "1_1") (pintype "passive"))
      (node (ref "R_PF3") (pin "2") (pinfunction "2_2") (pintype "passive"))
      (node (ref "R_T") (pin "2") (pinfunction "2_2") (pintype "passive"))
      (node (ref "R_T1") (pin "2") (pinfunction "2_2") (pintype "passive"))
      (node (ref "R_TST") (pin "2") (pinfunction "2_2") (pintype "passive"))
      (node (ref "X2") (pin "1") (pinfunction "S_1") (pintype "passive"))
    )
    (net (code "27") (name "/GPI") (class "Default")
      (node (ref "IC3") (pin "13-GPI") (pinfunction "GPI_13-GPI") (pintype "bidirectional"))
      (node (ref "R1") (pin "2") (pinfunction "2_2") (pintype "passive"))
      (node (ref "R_T1") (pin "1") (pinfunction "1_1") (pintype "passive"))
    )
    (net (code "28") (name "/I2C_SDA") (class "Default")
      (node (ref "IC15") (pin "2") (pinfunction "COM_2") (pintype "bidirectional"))
      (node (ref "IC3") (pin "5-SDA") (pinfunction "SDA_5-SDA") (pintype "bidirectional"))
    )
    (net (code "29") (name "/ICAP") (class "Default")
      (node (ref "IC3") (pin "25-ICAP") (pinfunction "ICAP_25-ICAP") (pintype "bidirectional"))
      (node (ref "L1") (pin "2") (pinfunction "2_2") (pintype "passive"))
      (node (ref "R_SNSC") (pin "1") (pinfunction "1_1") (pintype "passive"))
    )
    (net (code "30") (name "/ICSP_DI{slash}MISO") (class "Default")
      (node (ref "CONN1") (pin "2") (pinfunction "2_2") (pintype "bidirectional"))
      (node (ref "IC15") (pin "1") (pinfunction "NO_1") (pintype "bidirectional"))
      (node (ref "IC7") (pin "15") (pinfunction "MOSI/DI/SDA/PCINT5-PB5_15") (pintype "bidirectional"))
      (node (ref "R24") (pin "6") (pinfunction "6_6") (pintype "bidirectional"))
    )
    (net (code "31") (name "/ICSP_DO{slash}MOSI") (class "Default")
      (node (ref "CONN1") (pin "3") (pinfunction "3_3") (pintype "bidirectional"))
      (node (ref "IC7") (pin "16") (pinfunction "MISO/DO/PCINT6-PB6_16") (pintype "bidirectional"))
      (node (ref "R24") (pin "4") (pinfunction "4_4") (pintype "bidirectional"))
    )
    (net (code "32") (name "/ICSP_SCK") (class "Default")
      (node (ref "CONN1") (pin "4") (pinfunction "4_4") (pintype "bidirectional"))
      (node (ref "IC3") (pin "4-SCL") (pinfunction "SCL_4-SCL") (pintype "bidirectional"))
      (node (ref "IC7") (pin "17") (pinfunction "USCK/SCL/SCK/PCINT7-PB7_17") (pintype "bidirectional"))
      (node (ref "R24") (pin "2") (pinfunction "2_2") (pintype "bidirectional"))
    )
    (net (code "33") (name "/INT1") (class "Default")
      (node (ref "IC10") (pin "!INT!") (pinfunction "~{INT}_!INT!") (pintype "bidirectional"))
      (node (ref "IC7") (pin "5") (pinfunction "PCINT14/INT1-PD3_5") (pintype "bidirectional"))
    )
    (net (code "34") (name "/ITST") (class "Default")
      (node (ref "IC3") (pin "14-ITST") (pinfunction "ITST_14-ITST") (pintype "bidirectional"))
      (node (ref "R_TST") (pin "1") (pinfunction "1_1") (pintype "passive"))
    )
    (net (code "35") (name "/OUT+") (class "Default")
      (node (ref "C31") (pin "+") (pinfunction "+_+") (pintype "passive"))
      (node (ref "IC12") (pin "D1") (pinfunction "D1_D1") (pintype "bidirectional"))
      (node (ref "IC13") (pin "CATHODE") (pinfunction "CATHODE_CATHODE") (pintype "bidirectional"))
      (node (ref "IC8") (pin "CATHODE") (pinfunction "CATHODE_CATHODE") (pintype "bidirectional"))
      (node (ref "IC9") (pin "D2") (pinfunction "D2_D2") (pintype "bidirectional"))
      (node (ref "JP4") (pin "1") (pinfunction "1_1") (pintype "passive"))
    )
    (net (code "36") (name "/OUTFB") (class "Default")
      (node (ref "C5") (pin "2") (pinfunction "2_2") (pintype "passive"))
      (node (ref "IC3") (pin "10-OUTFB") (pinfunction "OUTFB_10-OUTFB") (pintype "bidirectional"))
      (node (ref "R_FB01") (pin "2") (pinfunction "2_2") (pintype "passive"))
      (node (ref "R_FB02") (pin "1") (pinfunction "1_1") (pintype "passive"))
    )
    (net (code "37") (name "/OV") (class "Default")
      (node (ref "IC3") (pin "43-OV") (pinfunction "OV_43-OV") (pintype "bidirectional"))
      (node (ref "R_PF2") (pin "2") (pinfunction "2_2") (pintype "passive"))
      (node (ref "R_PF3") (pin "1") (pinfunction "1_1") (pintype "passive"))
    )
    (net (code "38") (name "/RESET") (class "Default")
      (node (ref "IC10") (pin "!RESET!") (pinfunction "~{RESET}_!RESET!") (pintype "bidirectional"))
      (node (ref "R23") (pin "4") (pinfunction "4_4") (pintype "bidirectional"))
    )
    (net (code "39") (name "/RETRYB") (class "Default")
      (node (ref "IC3") (pin "34-RETRYB") (pinfunction "RETRYB_34-RETRYB") (pintype "bidirectional"))
      (node (ref "R13") (pin "1") (pinfunction "1_1") (pintype "passive"))
      (node (ref "R14") (pin "1") (pinfunction "1_1") (pintype "passive"))
    )
    (net (code "40") (name "/RT") (class "Default")
      (node (ref "IC3") (pin "12-RT") (pinfunction "RT_12-RT") (pintype "bidirectional"))
      (node (ref "R_T") (pin "1") (pinfunction "1_1") (pintype "passive"))
    )
    (net (code "41") (name "/RXCAN") (class "Default")
      (node (ref "IC10") (pin "RXCAN") (pinfunction "RXCAN_RXCAN") (pintype "input"))
      (node (ref "IC14") (pin "RXD") (pinfunction "RXD_RXD") (pintype "output"))
    )
    (net (code "42") (name "/SPI_MISO") (class "Default")
      (node (ref "IC10") (pin "SO") (pinfunction "SO_SO") (pintype "output"))
      (node (ref "R24") (pin "5") (pinfunction "5_5") (pintype "bidirectional"))
    )
    (net (code "43") (name "/SPI_MOSI") (class "Default")
      (node (ref "IC10") (pin "SI") (pinfunction "SI_SI") (pintype "input"))
      (node (ref "R24") (pin "3") (pinfunction "3_3") (pintype "bidirectional"))
    )
    (net (code "44") (name "/SPI_SCK") (class "Default")
      (node (ref "IC10") (pin "SCK") (pinfunction "SCK_SCK") (pintype "bidirectional"))
      (node (ref "R24") (pin "1") (pinfunction "1_1") (pintype "bidirectional"))
    )
    (net (code "45") (name "/SPI_SS") (class "Default")
      (node (ref "IC10") (pin "!CS!") (pinfunction "~{CS}_!CS!") (pintype "bidirectional"))
      (node (ref "IC15") (pin "4") (pinfunction "IN_4") (pintype "bidirectional"))
      (node (ref "IC7") (pin "14") (pinfunction "OC1B/PCINT4-PB4_14") (pintype "bidirectional"))
      (node (ref "R24") (pin "8") (pinfunction "8_8") (pintype "bidirectional"))
    )
    (net (code "46") (name "/STBY") (class "Default")
      (node (ref "IC14") (pin "STBY") (pinfunction "STBY_STBY") (pintype "bidirectional"))
      (node (ref "IC7") (pin "11") (pinfunction "AIN1/PCINT1-PB1_11") (pintype "bidirectional"))
      (node (ref "R23") (pin "2") (pinfunction "2_2") (pintype "bidirectional"))
    )
    (net (code "47") (name "/SW") (class "Default")
      (node (ref "C6") (pin "2") (pinfunction "2_2") (pintype "passive"))
      (node (ref "IC3") (pin "27-SW") (pinfunction "SW_27-SW") (pintype "bidirectional"))
      (node (ref "L1") (pin "1") (pinfunction "1_1") (pintype "passive"))
      (node (ref "MN2") (pin "4S") (pinfunction "S_4S") (pintype "passive"))
      (node (ref "MN2") (pin "S") (pinfunction "S_S") (pintype "passive"))
      (node (ref "MN3") (pin "1D") (pinfunction "D_1D") (pintype "passive"))
      (node (ref "MN3") (pin "2D") (pinfunction "D_2D") (pintype "passive"))
      (node (ref "MN3") (pin "5D") (pinfunction "D_5D") (pintype "passive"))
      (node (ref "MN3") (pin "6D") (pinfunction "D_6D") (pintype "passive"))
      (node (ref "MN3") (pin "D") (pinfunction "D_D") (pintype "passive"))
    )
    (net (code "48") (name "/TGATE") (class "Default")
      (node (ref "IC3") (pin "28-TGATE") (pinfunction "TGATE_28-TGATE") (pintype "bidirectional"))
      (node (ref "MN2") (pin "3G") (pinfunction "G_3G") (pintype "passive"))
    )
    (net (code "49") (name "/TXCAN") (class "Default")
      (node (ref "IC10") (pin "TXCAN") (pinfunction "TXCAN_TXCAN") (pintype "output"))
      (node (ref "IC14") (pin "TXD") (pinfunction "TXD_TXD") (pintype "input"))
    )
    (net (code "50") (name "/UV") (class "Default")
      (node (ref "IC3") (pin "42-UV") (pinfunction "UV_42-UV") (pintype "bidirectional"))
      (node (ref "R_PF1") (pin "2") (pinfunction "2_2") (pintype "passive"))
      (node (ref "R_PF2") (pin "1") (pinfunction "1_1") (pintype "passive"))
    )
    (net (code "51") (name "/VC") (class "Default")
      (node (ref "IC3") (pin "8-VC") (pinfunction "VC_8-VC") (pintype "bidirectional"))
      (node (ref "R2") (pin "1") (pinfunction "1_1") (pintype "passive"))
    )
    (net (code "52") (name "/VCAP") (class "Default")
      (node (ref "CAP4") (pin "+") (pinfunction "+_+") (pintype "passive"))
      (node (ref "C_CAP1") (pin "1") (pinfunction "1_1") (pintype "passive"))
      (node (ref "C_CAP2") (pin "1") (pinfunction "1_1") (pintype "passive"))
      (node (ref "C_CAP3") (pin "1") (pinfunction "1_1") (pintype "passive"))
      (node (ref "C_CAP4") (pin "1") (pinfunction "1_1") (pintype "passive"))
      (node (ref "C_CP5") (pin "1") (pinfunction "1_1") (pintype "passive"))
      (node (ref "IC3") (pin "24-VCAP") (pinfunction "VCAP_24-VCAP") (pintype "bidirectional"))
      (node (ref "R_CAP4") (pin "2") (pinfunction "2_2") (pintype "passive"))
      (node (ref "R_FBC1") (pin "2") (pinfunction "2_2") (pintype "passive"))
      (node (ref "R_SNSC") (pin "2") (pinfunction "2_2") (pintype "passive"))
    )
    (net (code "53") (name "/VCAPP5") (class "Default")
      (node (ref "C_CP5") (pin "2") (pinfunction "2_2") (pintype "passive"))
      (node (ref "IC3") (pin "22-VCAPP5") (pinfunction "VCAPP5_22-VCAPP5") (pintype "bidirectional"))
    )
    (net (code "54") (name "/VCC2P5") (class "Default")
      (node (ref "C1") (pin "1") (pinfunction "1_1") (pintype "passive"))
      (node (ref "IC3") (pin "1-CAP_SLCT0") (pinfunction "CAP_SLCT0_1-CAP_SLCT0") (pintype "bidirectional"))
      (node (ref "IC3") (pin "2-CAP_SLCT1") (pinfunction "CAP_SLCT1_2-CAP_SLCT1") (pintype "bidirectional"))
      (node (ref "IC3") (pin "26-VCC2P5") (pinfunction "VCC2P5_26-VCC2P5") (pintype "bidirectional"))
      (node (ref "R1") (pin "1") (pinfunction "1_1") (pintype "passive"))
    )
    (net (code "55") (name "/VDD") (class "Default")
      (node (ref "R3") (pin "1") (pinfunction "1_1") (pintype "passive"))
      (node (ref "R4") (pin "1") (pinfunction "1_1") (pintype "passive"))
      (node (ref "R8") (pin "1") (pinfunction "1_1") (pintype "passive"))
    )
    (net (code "56") (name "/VIN") (class "Default")
      (node (ref "MN1") (pin "1D") (pinfunction "D_1D") (pintype "passive"))
      (node (ref "MN1") (pin "2D") (pinfunction "D_2D") (pintype "passive"))
      (node (ref "MN1") (pin "5D") (pinfunction "D_5D") (pintype "passive"))
      (node (ref "MN1") (pin "6D") (pinfunction "D_6D") (pintype "passive"))
      (node (ref "MN1") (pin "D") (pinfunction "D_D") (pintype "passive"))
      (node (ref "R9") (pin "2") (pinfunction "2_2") (pintype "passive"))
      (node (ref "R_PF1") (pin "1") (pinfunction "1_1") (pintype "passive"))
    )
    (net (code "57") (name "/VOUT") (class "Default")
      (node (ref "C5") (pin "1") (pinfunction "1_1") (pintype "passive"))
      (node (ref "C_OUT1-1") (pin "1") (pinfunction "1_1") (pintype "passive"))
      (node (ref "C_OUT1-2") (pin "1") (pinfunction "1_1") (pintype "passive"))
      (node (ref "C_OUT1-3") (pin "1") (pinfunction "1_1") (pintype "passive"))
      (node (ref "C_OUT1-4") (pin "1") (pinfunction "1_1") (pintype "passive"))
      (node (ref "C_OUT1-5") (pin "1") (pinfunction "1_1") (pintype "passive"))
      (node (ref "C_OUT1-6") (pin "1") (pinfunction "1_1") (pintype "passive"))
      (node (ref "C_OUT2-1") (pin "1") (pinfunction "1_1") (pintype "passive"))
      (node (ref "C_OUT2-2") (pin "1") (pinfunction "1_1") (pintype "passive"))
      (node (ref "C_SS") (pin "1") (pinfunction "1_1") (pintype "passive"))
      (node (ref "IC3") (pin "33-VOUT") (pinfunction "VOUT_33-VOUT") (pintype "bidirectional"))
      (node (ref "IC3") (pin "35-ISNSM") (pinfunction "ISNSM_35-ISNSM") (pintype "bidirectional"))
      (node (ref "MN2") (pin "1D") (pinfunction "D_1D") (pintype "passive"))
      (node (ref "MN2") (pin "2D") (pinfunction "D_2D") (pintype "passive"))
      (node (ref "MN2") (pin "5D") (pinfunction "D_5D") (pintype "passive"))
      (node (ref "MN2") (pin "6D") (pinfunction "D_6D") (pintype "passive"))
      (node (ref "MN2") (pin "D") (pinfunction "D_D") (pintype "passive"))
      (node (ref "R14") (pin "2") (pinfunction "2_2") (pintype "passive"))
      (node (ref "R_FB01") (pin "1") (pinfunction "1_1") (pintype "passive"))
      (node (ref "R_SNSI") (pin "2") (pinfunction "2_2") (pintype "passive"))
    )
    (net (code "58") (name "/XTAL1") (class "Default")
      (node (ref "IC11") (pin "XTAL1") (pinfunction "XTAL1_XTAL1") (pintype "bidirectional"))
      (node (ref "IC7") (pin "3") (pinfunction "PCINT8/CLKI/XTAL1-PA0_3") (pintype "bidirectional"))
    )
    (net (code "59") (name "/XTAL2") (class "Default")
      (node (ref "IC11") (pin "XTAL2") (pinfunction "XTAL2_XTAL2") (pintype "bidirectional"))
      (node (ref "IC7") (pin "2") (pinfunction "PCINT9/XTAL2-PA1_2") (pintype "bidirectional"))
    )
    (net (code "60") (name "/ZERO_CROSS") (class "Default")
      (node (ref "IC16") (pin "1D") (pinfunction "D_1D") (pintype "passive"))
      (node (ref "IC16") (pin "2D") (pinfunction "D_2D") (pintype "passive"))
      (node (ref "IC16") (pin "5D") (pinfunction "D_5D") (pintype "passive"))
      (node (ref "IC16") (pin "6D") (pinfunction "D_6D") (pintype "passive"))
      (node (ref "IC16") (pin "D") (pinfunction "D_D") (pintype "passive"))
      (node (ref "JP8") (pin "1") (pinfunction "1_1") (pintype "passive"))
      (node (ref "R25") (pin "1") (pinfunction "1_1") (pintype "passive"))
    )
    (net (code "61") (name "/~{PFO}") (class "Default")
      (node (ref "IC3") (pin "3-VINGD") (pinfunction "VINGD_3-VINGD") (pintype "output"))
      (node (ref "R8") (pin "2") (pinfunction "2_2") (pintype "passive"))
    )
    (net (code "62") (name "/~{SMBALERT}") (class "Default")
      (node (ref "IC3") (pin "6-!SMBALERT!") (pinfunction "~{SMBALERT}_6-!SMBALERT!") (pintype "output"))
      (node (ref "IC7") (pin "12") (pinfunction "OC0A/PCINT2-PB2_12") (pintype "bidirectional"))
      (node (ref "R3") (pin "2") (pinfunction "2_2") (pintype "passive"))
    )
    (net (code "63") (name "Net-(C27-Pad1)") (class "Default")
      (node (ref "C27") (pin "1") (pinfunction "1_1") (pintype "passive"))
      (node (ref "IC6") (pin "VCAPL") (pinfunction "VCAPL_VCAPL") (pintype "bidirectional"))
    )
    (net (code "64") (name "Net-(C27-Pad2)") (class "Default")
      (node (ref "C27") (pin "2") (pinfunction "2_2") (pintype "passive"))
      (node (ref "IC6") (pin "VCAPH") (pinfunction "VCAPH_VCAPH") (pintype "bidirectional"))
    )
    (net (code "65") (name "Net-(C30-Pad1)") (class "Default")
      (node (ref "C30") (pin "1") (pinfunction "1_1") (pintype "passive"))
      (node (ref "IC8") (pin "VCAPL") (pinfunction "VCAPL_VCAPL") (pintype "bidirectional"))
    )
    (net (code "66") (name "Net-(C30-Pad2)") (class "Default")
      (node (ref "C30") (pin "2") (pinfunction "2_2") (pintype "passive"))
      (node (ref "IC8") (pin "VCAPH") (pinfunction "VCAPH_VCAPH") (pintype "bidirectional"))
    )
    (net (code "67") (name "Net-(C33-Pad1)") (class "Default")
      (node (ref "C33") (pin "1") (pinfunction "1_1") (pintype "passive"))
      (node (ref "IC13") (pin "VCAPL") (pinfunction "VCAPL_VCAPL") (pintype "bidirectional"))
    )
    (net (code "68") (name "Net-(C33-Pad2)") (class "Default")
      (node (ref "C33") (pin "2") (pinfunction "2_2") (pintype "passive"))
      (node (ref "IC13") (pin "VCAPH") (pinfunction "VCAPH_VCAPH") (pintype "bidirectional"))
    )
    (net (code "69") (name "Net-(C34-Pad1)") (class "Default")
      (node (ref "C34") (pin "1") (pinfunction "1_1") (pintype "passive"))
      (node (ref "IC17") (pin "VCAPL") (pinfunction "VCAPL_VCAPL") (pintype "bidirectional"))
    )
    (net (code "70") (name "Net-(C34-Pad2)") (class "Default")
      (node (ref "C34") (pin "2") (pinfunction "2_2") (pintype "passive"))
      (node (ref "IC17") (pin "VCAPH") (pinfunction "VCAPH_VCAPH") (pintype "bidirectional"))
    )
    (net (code "71") (name "Net-(CAP1-Pad+)") (class "Default")
      (node (ref "CAP1") (pin "+") (pinfunction "+_+") (pintype "passive"))
      (node (ref "CAP2") (pin "-") (pinfunction "-_-") (pintype "passive"))
      (node (ref "R_CAP1") (pin "2") (pinfunction "2_2") (pintype "passive"))
    )
    (net (code "72") (name "Net-(CAP2-Pad+)") (class "Default")
      (node (ref "CAP2") (pin "+") (pinfunction "+_+") (pintype "passive"))
      (node (ref "CAP3") (pin "-") (pinfunction "-_-") (pintype "passive"))
      (node (ref "R_CAP2") (pin "2") (pinfunction "2_2") (pintype "passive"))
    )
    (net (code "73") (name "Net-(CAP3-Pad+)") (class "Default")
      (node (ref "CAP3") (pin "+") (pinfunction "+_+") (pintype "passive"))
      (node (ref "CAP4") (pin "-") (pinfunction "-_-") (pintype "passive"))
      (node (ref "R_CAP3") (pin "2") (pinfunction "2_2") (pintype "passive"))
    )
    (net (code "74") (name "Net-(C_C-Pad1)") (class "Default")
      (node (ref "C_C") (pin "1") (pinfunction "1_1") (pintype "passive"))
      (node (ref "R2") (pin "2") (pinfunction "2_2") (pintype "passive"))
    )
    (net (code "75") (name "Net-(D2-PadCAT)") (class "Default")
      (node (ref "D2") (pin "CAT") (pinfunction "CAT_CAT") (pintype "passive"))
      (node (ref "D3") (pin "CAT") (pinfunction "CAT_CAT") (pintype "passive"))
    )
    (net (code "76") (name "Net-(IC3-CTIMER)") (class "Default")
      (node (ref "C3") (pin "2") (pinfunction "2_2") (pintype "passive"))
      (node (ref "IC3") (pin "44-CTIMER") (pinfunction "CTIMER_44-CTIMER") (pintype "bidirectional"))
    )
    (net (code "77") (name "Net-(IC3-HS_GATE)") (class "Default")
      (node (ref "IC3") (pin "40-HS_GATE") (pinfunction "HS_GATE_40-HS_GATE") (pintype "bidirectional"))
      (node (ref "R10") (pin "2") (pinfunction "2_2") (pintype "passive"))
      (node (ref "R11") (pin "1") (pinfunction "1_1") (pintype "passive"))
    )
    (net (code "78") (name "Net-(IC3-ISNSP_CHG)") (class "Default")
      (node (ref "IC3") (pin "36-ISNSP_CHG") (pinfunction "ISNSP_CHG_36-ISNSP_CHG") (pintype "bidirectional"))
      (node (ref "IC3") (pin "37-ISNS_HS") (pinfunction "ISNSP_HS_37-ISNS_HS") (pintype "bidirectional"))
      (node (ref "MN5") (pin "1D") (pinfunction "D_1D") (pintype "passive"))
      (node (ref "MN5") (pin "2D") (pinfunction "D_2D") (pintype "passive"))
      (node (ref "MN5") (pin "5D") (pinfunction "D_5D") (pintype "passive"))
      (node (ref "MN5") (pin "6D") (pinfunction "D_6D") (pintype "passive"))
      (node (ref "MN5") (pin "D") (pinfunction "D_D") (pintype "passive"))
      (node (ref "R_SNSI") (pin "1") (pinfunction "1_1") (pintype "passive"))
    )
    (net (code "79") (name "Net-(IC3-SRC)") (class "Default")
      (node (ref "IC3") (pin "39_SRC") (pinfunction "SRC_39_SRC") (pintype "power_in"))
      (node (ref "MN1") (pin "4S") (pinfunction "S_4S") (pintype "passive"))
      (node (ref "MN1") (pin "S") (pinfunction "S_S") (pintype "passive"))
      (node (ref "MN5") (pin "4S") (pinfunction "S_4S") (pintype "passive"))
      (node (ref "MN5") (pin "S") (pinfunction "S_S") (pintype "passive"))
    )
    (net (code "80") (name "Net-(IC3-VIN)") (class "Default")
      (node (ref "IC3") (pin "41-VIN") (pinfunction "VIN_41-VIN") (pintype "bidirectional"))
      (node (ref "R9") (pin "1") (pinfunction "1_1") (pintype "passive"))
    )
    (net (code "81") (name "Net-(IC14-PadSPLIT)") (class "Default")
      (node (ref "IC14") (pin "SPLIT") (pinfunction "SPLIT_SPLIT") (pintype "bidirectional"))
      (node (ref "TP1") (pin "TP") (pinfunction "TP_TP") (pintype "input"))
    )
    (net (code "82") (name "Net-(JP4-Pad2)") (class "Default")
      (node (ref "JP4") (pin "2") (pinfunction "2_2") (pintype "passive"))
      (node (ref "JP6") (pin "1") (pinfunction "1_1") (pintype "passive"))
    )
    (net (code "83") (name "Net-(MN1-G)") (class "Default")
      (node (ref "MN1") (pin "3G") (pinfunction "G_3G") (pintype "passive"))
      (node (ref "R10") (pin "1") (pinfunction "1_1") (pintype "passive"))
    )
    (net (code "84") (name "Net-(MN5-G)") (class "Default")
      (node (ref "MN5") (pin "3G") (pinfunction "G_3G") (pintype "passive"))
      (node (ref "R11") (pin "2") (pinfunction "2_2") (pintype "passive"))
    )
    (net (code "85") (name "unconnected-(IC3-OUTFET-Pad23-OUTFET)") (class "Default")
      (node (ref "IC3") (pin "23-OUTFET") (pinfunction "OUTFET_23-OUTFET") (pintype "bidirectional"))
    )
    (net (code "86") (name "unconnected-(IC7-AIN0{slash}PCINT0-PB0-Pad10)") (class "Default")
      (node (ref "IC7") (pin "10") (pinfunction "AIN0/PCINT0-PB0_10") (pintype "bidirectional"))
    )
    (net (code "87") (name "unconnected-(IC7-OC1A{slash}PCINT3-PB3-Pad13)") (class "Default")
      (node (ref "IC7") (pin "13") (pinfunction "OC1A/PCINT3-PB3_13") (pintype "bidirectional"))
    )
    (net (code "88") (name "unconnected-(IC7-PCINT12{slash}TXD-PD1-Pad1)") (class "Default")
      (node (ref "IC7") (pin "1") (pinfunction "PCINT12/TXD-PD1_1") (pintype "bidirectional"))
    )
    (net (code "89") (name "unconnected-(IC7-PCINT15{slash}T0-PD4-Pad6)") (class "Default")
      (node (ref "IC7") (pin "6") (pinfunction "PCINT15/T0-PD4_6") (pintype "bidirectional"))
    )
    (net (code "90") (name "unconnected-(IC7-PCINT16{slash}OC0B{slash}T1-PD5-Pad7)") (class "Default")
      (node (ref "IC7") (pin "7") (pinfunction "PCINT16/OC0B/T1-PD5_7") (pintype "bidirectional"))
    )
    (net (code "91") (name "unconnected-(IC7-PCINT17{slash}ICPI-PD6-Pad9)") (class "Default")
      (node (ref "IC7") (pin "9") (pinfunction "PCINT17/ICPI-PD6_9") (pintype "bidirectional"))
    )
    (net (code "92") (name "unconnected-(IC7-RXD{slash}PCINT11-PD0-Pad20)") (class "Default")
      (node (ref "IC7") (pin "20") (pinfunction "RXD/PCINT11-PD0_20") (pintype "bidirectional"))
    )
    (net (code "93") (name "unconnected-(IC10-NC-PadNC1)") (class "Default")
      (node (ref "IC10") (pin "NC1") (pinfunction "NC_NC1") (pintype "no_connect"))
    )
    (net (code "94") (name "unconnected-(IC10-NC-PadNC2)") (class "Default")
      (node (ref "IC10") (pin "NC2") (pinfunction "NC_NC2") (pintype "no_connect"))
    )
    (net (code "95") (name "unconnected-(IC10-PadCLKOUT)") (class "Default")
      (node (ref "IC10") (pin "CLKOUT") (pinfunction "CLKOUT_CLKOUT") (pintype "bidirectional"))
    )
    (net (code "96") (name "unconnected-(IC10-PadOSC2)") (class "Default")
      (node (ref "IC10") (pin "OSC2") (pinfunction "OSC2_OSC2") (pintype "bidirectional"))
    )
    (net (code "97") (name "unconnected-(IC10-~{RX0BF}-Pad!RX0BF!)") (class "Default")
      (node (ref "IC10") (pin "!RX0BF!") (pinfunction "~{RX0BF}_!RX0BF!") (pintype "bidirectional"))
    )
    (net (code "98") (name "unconnected-(IC10-~{RX1BF}-Pad!RX1BF!)") (class "Default")
      (node (ref "IC10") (pin "!RX1BF!") (pinfunction "~{RX1BF}_!RX1BF!") (pintype "bidirectional"))
    )
    (net (code "99") (name "unconnected-(IC10-~{TX0RTS}-Pad!TX0RTS!)") (class "Default")
      (node (ref "IC10") (pin "!TX0RTS!") (pinfunction "~{TX0RTS}_!TX0RTS!") (pintype "bidirectional"))
    )
    (net (code "100") (name "unconnected-(IC10-~{TX1RTS}-Pad!TX1RTS!)") (class "Default")
      (node (ref "IC10") (pin "!TX1RTS!") (pinfunction "~{TX1RTS}_!TX1RTS!") (pintype "bidirectional"))
    )
    (net (code "101") (name "unconnected-(IC10-~{TX2RTS}-Pad!TX2RTS!)") (class "Default")
      (node (ref "IC10") (pin "!TX2RTS!") (pinfunction "~{TX2RTS}_!TX2RTS!") (pintype "bidirectional"))
    )
    (net (code "102") (name "unconnected-(JP1-Pad1)") (class "Default")
      (node (ref "JP1") (pin "1") (pinfunction "1_1") (pintype "passive"))
    )
    (net (code "103") (name "unconnected-(JP1-Pad2)") (class "Default")
      (node (ref "JP1") (pin "2") (pinfunction "2_2") (pintype "passive"))
    )
    (net (code "104") (name "unconnected-(JP2-Pad1)") (class "Default")
      (node (ref "JP2") (pin "1") (pinfunction "1_1") (pintype "passive"))
    )
    (net (code "105") (name "unconnected-(JP2-Pad2)") (class "Default")
      (node (ref "JP2") (pin "2") (pinfunction "2_2") (pintype "passive"))
    )
    (net (code "106") (name "unconnected-(JP3-Pad1)") (class "Default")
      (node (ref "JP3") (pin "1") (pinfunction "1_1") (pintype "passive"))
    )
    (net (code "107") (name "unconnected-(JP3-Pad2)") (class "Default")
      (node (ref "JP3") (pin "2") (pinfunction "2_2") (pintype "passive"))
    )
    (net (code "108") (name "unconnected-(JP5-Pad1)") (class "Default")
      (node (ref "JP5") (pin "1") (pinfunction "1_1") (pintype "passive"))
    )
    (net (code "109") (name "unconnected-(JP5-Pad2)") (class "Default")
      (node (ref "JP5") (pin "2") (pinfunction "2_2") (pintype "passive"))
    )
    (net (code "110") (name "unconnected-(R23-Pad5)") (class "Default")
      (node (ref "R23") (pin "5") (pinfunction "5_5") (pintype "bidirectional"))
    )
    (net (code "111") (name "unconnected-(R23-Pad6)") (class "Default")
      (node (ref "R23") (pin "6") (pinfunction "6_6") (pintype "bidirectional"))
    )
    (net (code "112") (name "unconnected-(R23-Pad7)") (class "Default")
      (node (ref "R23") (pin "7") (pinfunction "7_7") (pintype "bidirectional"))
    )
    (net (code "113") (name "unconnected-(R23-Pad8)") (class "Default")
      (node (ref "R23") (pin "8") (pinfunction "8_8") (pintype "bidirectional"))
    )
  )
)
